# CON_PS2MOUSE_MINIDIN6F.net
KiCad netlist of a schematic drawn in Altium Designer
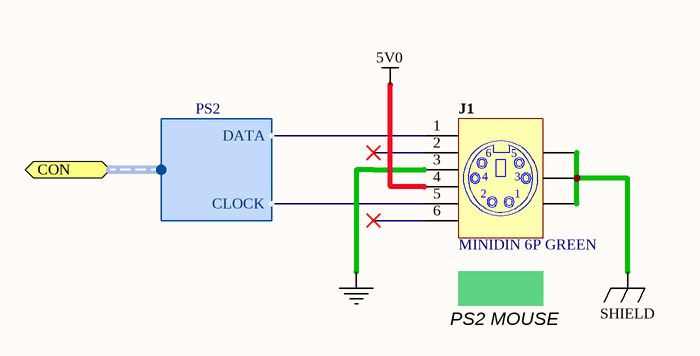
[diagram p0: CON_PS2MOUSE_MINIDIN6F.SchDoc]

(export (version "E")
  (design (tool "Eeschema 10.0.6"))
  (components
    (comp (ref "J1")
      (value "MINIDIN 6P GREEN")
      (footprint "MINIDIN6GREEN")
      (description "MINI-DIN R/A F/SHLD 6P GOLD PLATED--GREEN PC99 RoHS Compliant")
      (libsource (lib "AltiumDesignLibrary") (part "CON-MINIDIN-6-F"))
    )
  )
  (nets
    (net (code "2") (name "/CLOCK") (class "Default")
      (node (ref "J1") (pin "5") (pinfunction "5_5") (pintype "passive"))
    )
    (net (code "3") (name "/DATA") (class "Default")
      (node (ref "J1") (pin "1") (pinfunction "1_1") (pintype "passive"))
    )
    (net (code "5") (name "5V0") (class "Default")
      (node (ref "J1") (pin "4") (pinfunction "4_4") (pintype "passive"))
    )
    (net (code "6") (name "GND") (class "Default")
      (node (ref "J1") (pin "3") (pinfunction "3_3") (pintype "passive"))
    )
    (net (code "7") (name "SHIELD") (class "Default")
      (node (ref "J1") (pin "MH1") (pinfunction "MH1_MH1") (pintype "passive"))
      (node (ref "J1") (pin "MH2") (pinfunction "MH2_MH2") (pintype "passive"))
      (node (ref "J1") (pin "MH3") (pinfunction "MH3_MH3") (pintype "passive"))
    )
    (net (code "8") (name "unconnected-(J1-Pad2)") (class "Default")
      (node (ref "J1") (pin "2") (pinfunction "2_2") (pintype "passive+no_connect"))
    )
    (net (code "9") (name "unconnected-(J1-Pad6)") (class "Default")
      (node (ref "J1") (pin "6") (pinfunction "6_6") (pintype "passive+no_connect"))
    )
  )
)
